# Lift_M.net
KiCad netlist of a schematic drawn in EAGLE
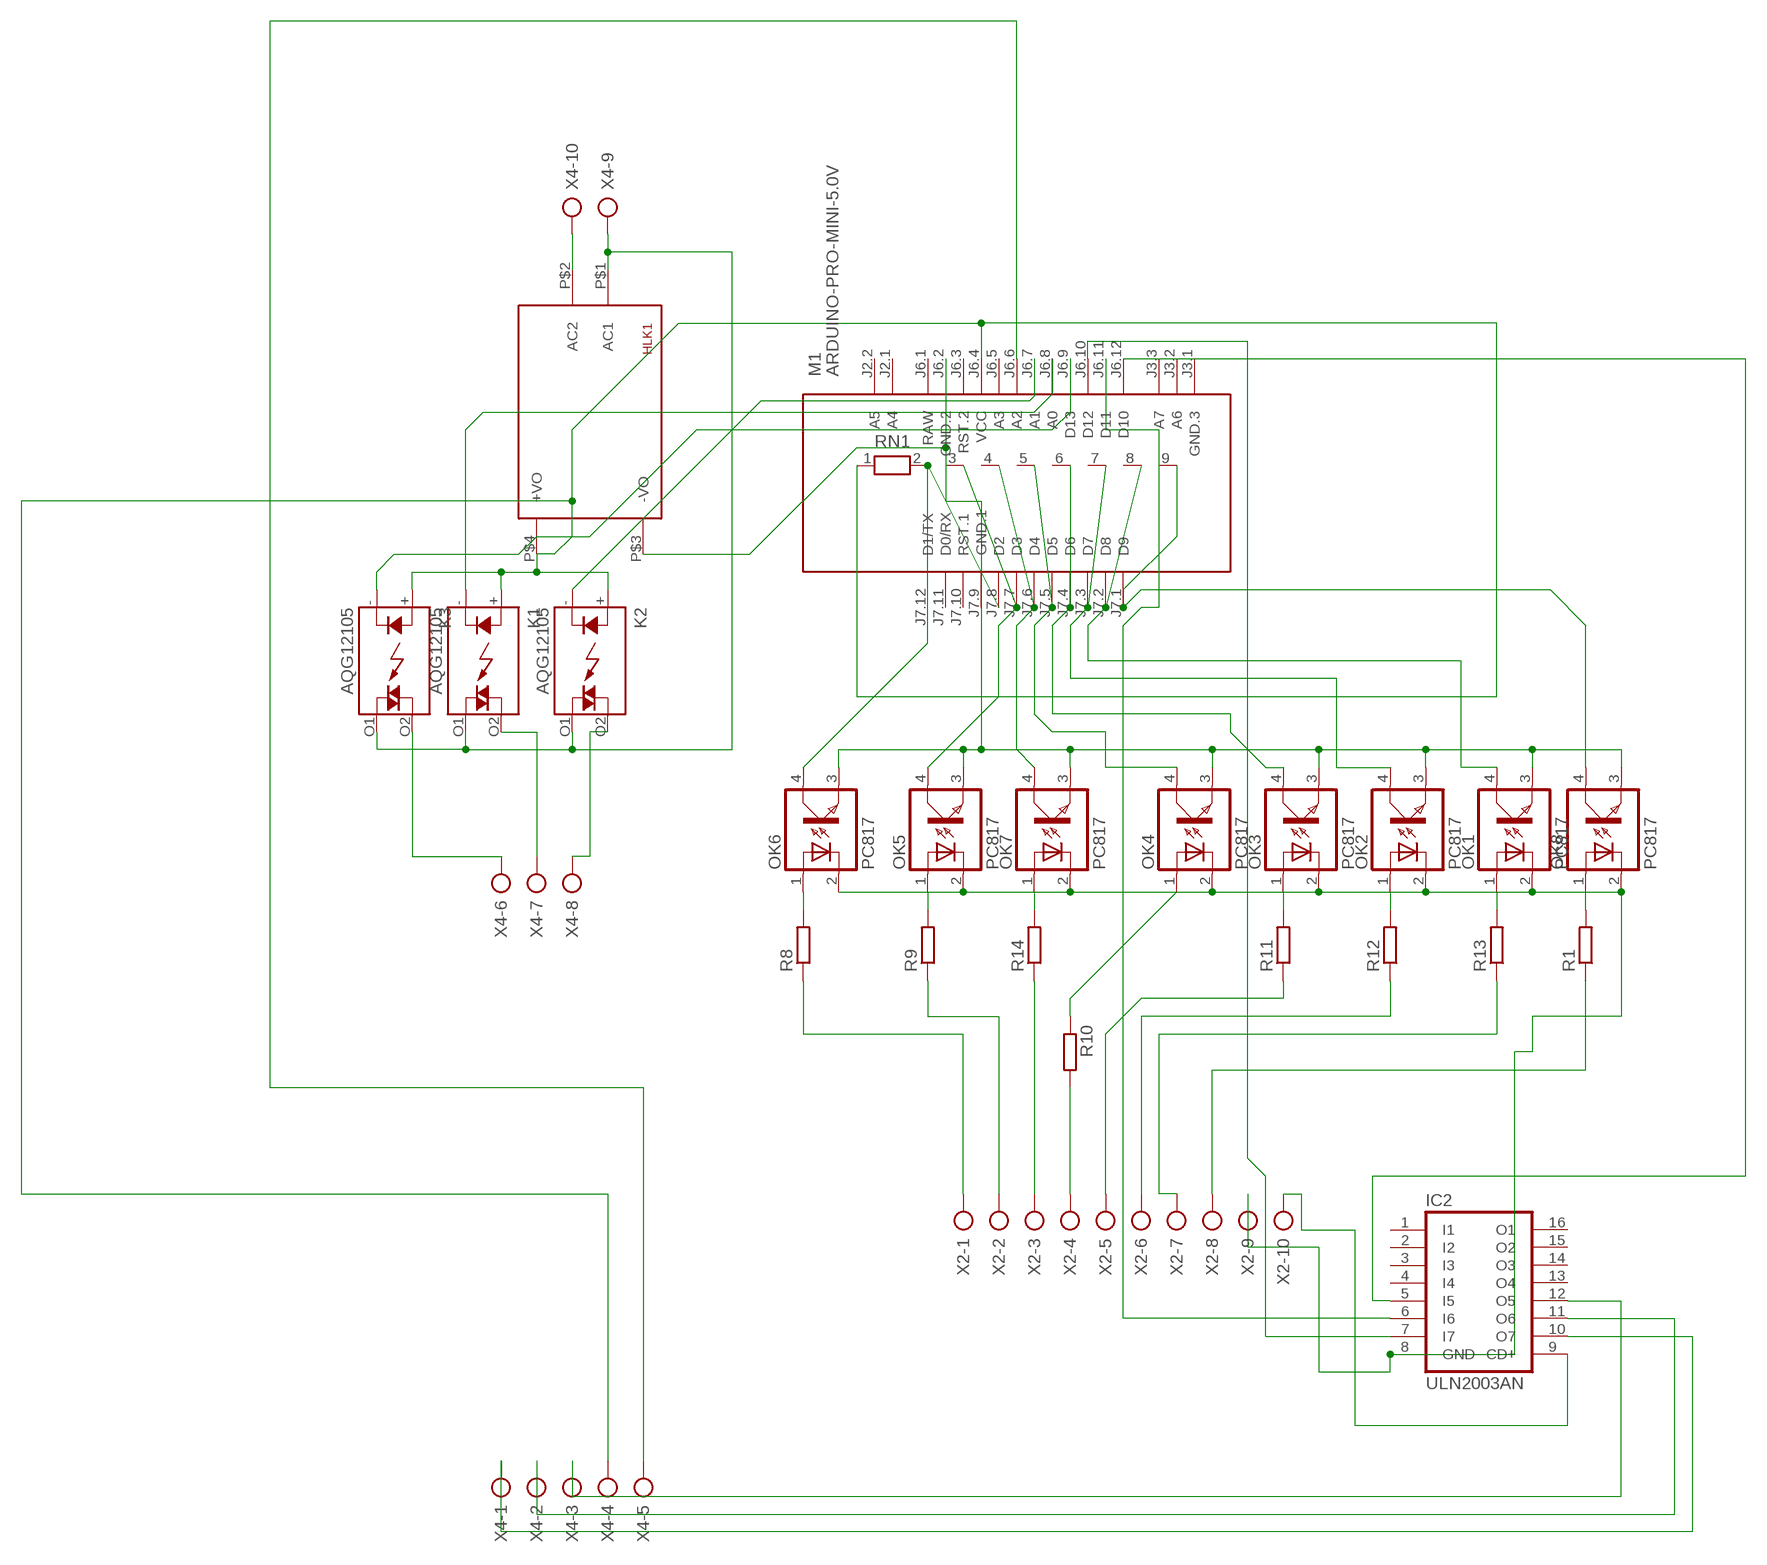
[diagram p0: schematic, sheet 1]

(export (version "E")
  (design (tool "Eeschema 10.0.6"))
  (components
    (comp (ref "HLK1")
      (value "HLK-PM013W")
      (footprint "eagle-import:HLK-PM01")
      (libsource (lib "eagle-import") (part "HLK-PM013W"))
    )
    (comp (ref "IC2")
      (value "ULN2003AN")
      (footprint "eagle-import:DIL16")
      (libsource (lib "eagle-import") (part "ULN2003AN"))
    )
    (comp (ref "K1")
      (value "AQG12105")
      (footprint "eagle-import:AQG")
      (fields (field (name "MF") "AROMAT/ MATSUSHITA"))
      (libsource (lib "eagle-import") (part "AQG12105"))
    )
    (comp (ref "K2")
      (value "AQG12105")
      (footprint "eagle-import:AQG")
      (fields (field (name "MF") "AROMAT/ MATSUSHITA"))
      (libsource (lib "eagle-import") (part "AQG12105"))
    )
    (comp (ref "K3")
      (value "AQG12105")
      (footprint "eagle-import:AQG")
      (fields (field (name "MF") "AROMAT/ MATSUSHITA"))
      (libsource (lib "eagle-import") (part "AQG12105"))
    )
    (comp (ref "M1")
      (value "ARDUINO-PRO-MINI-5.0V")
      (footprint "eagle-import:ARDUINO-PRO-MINI")
      (libsource (lib "eagle-import") (part "ARDUINO-PRO-MINI-5.0V"))
    )
    (comp (ref "OK1")
      (value "PC817")
      (footprint "eagle-import:DIL04")
      (fields (field (name "MPN") "PC817X4J000F"))
      (libsource (lib "eagle-import") (part "PC817"))
    )
    (comp (ref "OK2")
      (value "PC817")
      (footprint "eagle-import:DIL04")
      (fields (field (name "MPN") "PC817X4J000F"))
      (libsource (lib "eagle-import") (part "PC817"))
    )
    (comp (ref "OK3")
      (value "PC817")
      (footprint "eagle-import:DIL04")
      (fields (field (name "MPN") "PC817X4J000F"))
      (libsource (lib "eagle-import") (part "PC817"))
    )
    (comp (ref "OK4")
      (value "PC817")
      (footprint "eagle-import:DIL04")
      (fields (field (name "MPN") "PC817X4J000F"))
      (libsource (lib "eagle-import") (part "PC817"))
    )
    (comp (ref "OK5")
      (value "PC817")
      (footprint "eagle-import:DIL04")
      (fields (field (name "MPN") "PC817X4J000F"))
      (libsource (lib "eagle-import") (part "PC817"))
    )
    (comp (ref "OK6")
      (value "PC817")
      (footprint "eagle-import:DIL04")
      (fields (field (name "MPN") "PC817X4J000F"))
      (libsource (lib "eagle-import") (part "PC817"))
    )
    (comp (ref "OK7")
      (value "PC817")
      (footprint "eagle-import:DIL04")
      (fields (field (name "MPN") "PC817X4J000F"))
      (libsource (lib "eagle-import") (part "PC817"))
    )
    (comp (ref "OK8")
      (value "PC817")
      (footprint "eagle-import:DIL04")
      (fields (field (name "MPN") "PC817X4J000F"))
      (libsource (lib "eagle-import") (part "PC817"))
    )
    (comp (ref "R1")
      (value "R-EU_0204/7")
      (footprint "eagle-import:0204_7")
      (libsource (lib "eagle-import") (part "R-EU_0204/7"))
    )
    (comp (ref "R8")
      (value "R-EU_0204/7")
      (footprint "eagle-import:0204_7")
      (libsource (lib "eagle-import") (part "R-EU_0204/7"))
    )
    (comp (ref "R9")
      (value "R-EU_0204/7")
      (footprint "eagle-import:0204_7")
      (libsource (lib "eagle-import") (part "R-EU_0204/7"))
    )
    (comp (ref "R10")
      (value "R-EU_0204/7")
      (footprint "eagle-import:0204_7")
      (libsource (lib "eagle-import") (part "R-EU_0204/7"))
    )
    (comp (ref "R11")
      (value "R-EU_0204/7")
      (footprint "eagle-import:0204_7")
      (libsource (lib "eagle-import") (part "R-EU_0204/7"))
    )
    (comp (ref "R12")
      (value "R-EU_0204/7")
      (footprint "eagle-import:0204_7")
      (libsource (lib "eagle-import") (part "R-EU_0204/7"))
    )
    (comp (ref "R13")
      (value "R-EU_0204/7")
      (footprint "eagle-import:0204_7")
      (libsource (lib "eagle-import") (part "R-EU_0204/7"))
    )
    (comp (ref "R14")
      (value "R-EU_0204/7")
      (footprint "eagle-import:0204_7")
      (libsource (lib "eagle-import") (part "R-EU_0204/7"))
    )
    (comp (ref "RN1")
      (value "RN08")
      (footprint "eagle-import:RN-9")
      (libsource (lib "eagle-import") (part "RN08"))
    )
    (comp (ref "X2")
      (value "AK300/10")
      (footprint "eagle-import:AK300_10")
      (libsource (lib "eagle-import") (part "AK300/10"))
    )
    (comp (ref "X4")
      (value "AK300/10")
      (footprint "eagle-import:AK300_10")
      (libsource (lib "eagle-import") (part "AK300/10"))
    )
  )
  (nets
    (net (code "1") (name "/RAW") (class "Default")
      (node (ref "M1") (pin "J6.1") (pinfunction "RAW_J6.1") (pintype "power_in"))
    )
    (net (code "2") (name "Net-(HLK1-+VO)") (class "Default")
      (node (ref "HLK1") (pin "P$4") (pinfunction "+VO_P$4") (pintype "bidirectional"))
      (node (ref "K1") (pin "+") (pinfunction "A_+") (pintype "passive"))
      (node (ref "K2") (pin "+") (pinfunction "A_+") (pintype "passive"))
      (node (ref "K3") (pin "+") (pinfunction "A_+") (pintype "passive"))
      (node (ref "M1") (pin "J6.4") (pinfunction "VCC_J6.4") (pintype "power_in"))
      (node (ref "RN1") (pin "1") (pinfunction "1_1") (pintype "passive"))
      (node (ref "X4") (pin "4") (pinfunction "KL_4") (pintype "passive"))
    )
    (net (code "3") (name "Net-(HLK1--VO)") (class "Default")
      (node (ref "HLK1") (pin "P$3") (pinfunction "-VO_P$3") (pintype "bidirectional"))
      (node (ref "M1") (pin "J6.2") (pinfunction "GND.2_J6.2") (pintype "power_in"))
      (node (ref "M1") (pin "J7.9") (pinfunction "GND.1_J7.9") (pintype "power_in"))
      (node (ref "OK1") (pin "3") (pinfunction "EMIT_3") (pintype "passive"))
      (node (ref "OK2") (pin "3") (pinfunction "EMIT_3") (pintype "passive"))
      (node (ref "OK3") (pin "3") (pinfunction "EMIT_3") (pintype "passive"))
      (node (ref "OK4") (pin "3") (pinfunction "EMIT_3") (pintype "passive"))
      (node (ref "OK5") (pin "3") (pinfunction "EMIT_3") (pintype "passive"))
      (node (ref "OK6") (pin "3") (pinfunction "EMIT_3") (pintype "passive"))
      (node (ref "OK7") (pin "3") (pinfunction "EMIT_3") (pintype "passive"))
      (node (ref "OK8") (pin "3") (pinfunction "EMIT_3") (pintype "passive"))
    )
    (net (code "4") (name "Net-(HLK1-AC1)") (class "Default")
      (node (ref "HLK1") (pin "P$1") (pinfunction "AC1_P$1") (pintype "bidirectional"))
      (node (ref "K1") (pin "O1") (pinfunction "DS2_O1") (pintype "passive"))
      (node (ref "K2") (pin "O1") (pinfunction "DS2_O1") (pintype "passive"))
      (node (ref "K3") (pin "O1") (pinfunction "DS2_O1") (pintype "passive"))
      (node (ref "X4") (pin "9") (pinfunction "KL_9") (pintype "passive"))
    )
    (net (code "5") (name "Net-(HLK1-AC2)") (class "Default")
      (node (ref "HLK1") (pin "P$2") (pinfunction "AC2_P$2") (pintype "bidirectional"))
      (node (ref "X4") (pin "10") (pinfunction "KL_10") (pintype "passive"))
    )
    (net (code "6") (name "Net-(IC2-CD+)") (class "Default")
      (node (ref "IC2") (pin "9") (pinfunction "CD+_9") (pintype "passive"))
      (node (ref "X2") (pin "10") (pinfunction "KL_10") (pintype "passive"))
    )
    (net (code "7") (name "Net-(IC2-GND)") (class "Default")
      (node (ref "IC2") (pin "8") (pinfunction "GND_8") (pintype "power_in"))
      (node (ref "OK1") (pin "2") (pinfunction "C_2") (pintype "passive"))
      (node (ref "OK2") (pin "2") (pinfunction "C_2") (pintype "passive"))
      (node (ref "OK3") (pin "2") (pinfunction "C_2") (pintype "passive"))
      (node (ref "OK4") (pin "2") (pinfunction "C_2") (pintype "passive"))
      (node (ref "OK5") (pin "2") (pinfunction "C_2") (pintype "passive"))
      (node (ref "OK6") (pin "2") (pinfunction "C_2") (pintype "passive"))
      (node (ref "OK7") (pin "2") (pinfunction "C_2") (pintype "passive"))
      (node (ref "OK8") (pin "2") (pinfunction "C_2") (pintype "passive"))
      (node (ref "X2") (pin "9") (pinfunction "KL_9") (pintype "passive"))
    )
    (net (code "8") (name "Net-(IC2-I5)") (class "Default")
      (node (ref "IC2") (pin "5") (pinfunction "I5_5") (pintype "input"))
      (node (ref "M1") (pin "J6.12") (pinfunction "D10_J6.12") (pintype "bidirectional"))
    )
    (net (code "9") (name "Net-(IC2-I6)") (class "Default")
      (node (ref "IC2") (pin "6") (pinfunction "I6_6") (pintype "input"))
      (node (ref "M1") (pin "J6.11") (pinfunction "D11_J6.11") (pintype "bidirectional"))
    )
    (net (code "10") (name "Net-(IC2-I7)") (class "Default")
      (node (ref "IC2") (pin "7") (pinfunction "I7_7") (pintype "input"))
      (node (ref "M1") (pin "J6.10") (pinfunction "D12_J6.10") (pintype "bidirectional"))
    )
    (net (code "11") (name "Net-(IC2-O5)") (class "Default")
      (node (ref "IC2") (pin "12") (pinfunction "O5_12") (pintype "open_collector"))
      (node (ref "X4") (pin "3") (pinfunction "KL_3") (pintype "passive"))
    )
    (net (code "12") (name "Net-(IC2-O6)") (class "Default")
      (node (ref "IC2") (pin "11") (pinfunction "O6_11") (pintype "open_collector"))
      (node (ref "X4") (pin "2") (pinfunction "KL_2") (pintype "passive"))
    )
    (net (code "13") (name "Net-(IC2-O7)") (class "Default")
      (node (ref "IC2") (pin "10") (pinfunction "O7_10") (pintype "open_collector"))
      (node (ref "X4") (pin "1") (pinfunction "KL_1") (pintype "passive"))
    )
    (net (code "14") (name "Net-(K1-DS1)") (class "Default")
      (node (ref "K1") (pin "O2") (pinfunction "DS1_O2") (pintype "passive"))
      (node (ref "X4") (pin "7") (pinfunction "KL_7") (pintype "passive"))
    )
    (net (code "15") (name "Net-(K1-K)") (class "Default")
      (node (ref "K1") (pin "-") (pinfunction "K_-") (pintype "passive"))
      (node (ref "M1") (pin "J6.8") (pinfunction "A0_J6.8") (pintype "bidirectional"))
    )
    (net (code "16") (name "Net-(K2-DS1)") (class "Default")
      (node (ref "K2") (pin "O2") (pinfunction "DS1_O2") (pintype "passive"))
      (node (ref "X4") (pin "8") (pinfunction "KL_8") (pintype "passive"))
    )
    (net (code "17") (name "Net-(K2-K)") (class "Default")
      (node (ref "K2") (pin "-") (pinfunction "K_-") (pintype "passive"))
      (node (ref "M1") (pin "J6.7") (pinfunction "A1_J6.7") (pintype "bidirectional"))
    )
    (net (code "18") (name "Net-(K3-DS1)") (class "Default")
      (node (ref "K3") (pin "O2") (pinfunction "DS1_O2") (pintype "passive"))
      (node (ref "X4") (pin "6") (pinfunction "KL_6") (pintype "passive"))
    )
    (net (code "19") (name "Net-(K3-K)") (class "Default")
      (node (ref "K3") (pin "-") (pinfunction "K_-") (pintype "passive"))
      (node (ref "M1") (pin "J6.9") (pinfunction "D13_J6.9") (pintype "bidirectional"))
    )
    (net (code "20") (name "Net-(M1-A2)") (class "Default")
      (node (ref "M1") (pin "J6.6") (pinfunction "A2_J6.6") (pintype "bidirectional"))
      (node (ref "X4") (pin "5") (pinfunction "KL_5") (pintype "passive"))
    )
    (net (code "21") (name "Net-(M1-D2)") (class "Default")
      (node (ref "M1") (pin "J7.8") (pinfunction "D2_J7.8") (pintype "bidirectional"))
      (node (ref "OK6") (pin "4") (pinfunction "COL_4") (pintype "passive"))
      (node (ref "RN1") (pin "2") (pinfunction "2_2") (pintype "passive"))
    )
    (net (code "22") (name "Net-(M1-D3)") (class "Default")
      (node (ref "M1") (pin "J7.7") (pinfunction "D3_J7.7") (pintype "bidirectional"))
      (node (ref "OK5") (pin "4") (pinfunction "COL_4") (pintype "passive"))
      (node (ref "RN1") (pin "3") (pinfunction "3_3") (pintype "passive"))
    )
    (net (code "23") (name "Net-(M1-D4)") (class "Default")
      (node (ref "M1") (pin "J7.6") (pinfunction "D4_J7.6") (pintype "bidirectional"))
      (node (ref "OK7") (pin "4") (pinfunction "COL_4") (pintype "passive"))
      (node (ref "RN1") (pin "4") (pinfunction "4_4") (pintype "passive"))
    )
    (net (code "24") (name "Net-(M1-D5)") (class "Default")
      (node (ref "M1") (pin "J7.5") (pinfunction "D5_J7.5") (pintype "bidirectional"))
      (node (ref "OK4") (pin "4") (pinfunction "COL_4") (pintype "passive"))
      (node (ref "RN1") (pin "5") (pinfunction "5_5") (pintype "passive"))
    )
    (net (code "25") (name "Net-(M1-D6)") (class "Default")
      (node (ref "M1") (pin "J7.4") (pinfunction "D6_J7.4") (pintype "bidirectional"))
      (node (ref "OK3") (pin "4") (pinfunction "COL_4") (pintype "passive"))
      (node (ref "RN1") (pin "6") (pinfunction "6_6") (pintype "passive"))
    )
    (net (code "26") (name "Net-(M1-D7)") (class "Default")
      (node (ref "M1") (pin "J7.3") (pinfunction "D7_J7.3") (pintype "bidirectional"))
      (node (ref "OK2") (pin "4") (pinfunction "COL_4") (pintype "passive"))
      (node (ref "RN1") (pin "7") (pinfunction "7_7") (pintype "passive"))
    )
    (net (code "27") (name "Net-(M1-D8)") (class "Default")
      (node (ref "M1") (pin "J7.2") (pinfunction "D8_J7.2") (pintype "bidirectional"))
      (node (ref "OK1") (pin "4") (pinfunction "COL_4") (pintype "passive"))
      (node (ref "RN1") (pin "8") (pinfunction "8_8") (pintype "passive"))
    )
    (net (code "28") (name "Net-(M1-D9)") (class "Default")
      (node (ref "M1") (pin "J7.1") (pinfunction "D9_J7.1") (pintype "bidirectional"))
      (node (ref "OK8") (pin "4") (pinfunction "COL_4") (pintype "passive"))
      (node (ref "RN1") (pin "9") (pinfunction "9_9") (pintype "passive"))
    )
    (net (code "29") (name "Net-(OK1-A)") (class "Default")
      (node (ref "OK1") (pin "1") (pinfunction "A_1") (pintype "passive"))
      (node (ref "R13") (pin "2") (pinfunction "2_2") (pintype "passive"))
    )
    (net (code "30") (name "Net-(OK2-A)") (class "Default")
      (node (ref "OK2") (pin "1") (pinfunction "A_1") (pintype "passive"))
      (node (ref "R12") (pin "2") (pinfunction "2_2") (pintype "passive"))
    )
    (net (code "31") (name "Net-(OK3-A)") (class "Default")
      (node (ref "OK3") (pin "1") (pinfunction "A_1") (pintype "passive"))
      (node (ref "R11") (pin "2") (pinfunction "2_2") (pintype "passive"))
    )
    (net (code "32") (name "Net-(OK4-A)") (class "Default")
      (node (ref "OK4") (pin "1") (pinfunction "A_1") (pintype "passive"))
      (node (ref "R10") (pin "1") (pinfunction "1_1") (pintype "passive"))
    )
    (net (code "33") (name "Net-(OK5-A)") (class "Default")
      (node (ref "OK5") (pin "1") (pinfunction "A_1") (pintype "passive"))
      (node (ref "R9") (pin "2") (pinfunction "2_2") (pintype "passive"))
    )
    (net (code "34") (name "Net-(OK6-A)") (class "Default")
      (node (ref "OK6") (pin "1") (pinfunction "A_1") (pintype "passive"))
      (node (ref "R8") (pin "2") (pinfunction "2_2") (pintype "passive"))
    )
    (net (code "35") (name "Net-(OK7-A)") (class "Default")
      (node (ref "OK7") (pin "1") (pinfunction "A_1") (pintype "passive"))
      (node (ref "R14") (pin "2") (pinfunction "2_2") (pintype "passive"))
    )
    (net (code "36") (name "Net-(OK8-A)") (class "Default")
      (node (ref "OK8") (pin "1") (pinfunction "A_1") (pintype "passive"))
      (node (ref "R1") (pin "2") (pinfunction "2_2") (pintype "passive"))
    )
    (net (code "37") (name "Net-(X2A-KL)") (class "Default")
      (node (ref "R8") (pin "1") (pinfunction "1_1") (pintype "passive"))
      (node (ref "X2") (pin "1") (pinfunction "KL_1") (pintype "passive"))
    )
    (net (code "38") (name "Net-(X2C-KL)") (class "Default")
      (node (ref "R9") (pin "1") (pinfunction "1_1") (pintype "passive"))
      (node (ref "X2") (pin "2") (pinfunction "KL_2") (pintype "passive"))
    )
    (net (code "39") (name "Net-(X2D-KL)") (class "Default")
      (node (ref "R14") (pin "1") (pinfunction "1_1") (pintype "passive"))
      (node (ref "X2") (pin "3") (pinfunction "KL_3") (pintype "passive"))
    )
    (net (code "40") (name "Net-(X2E-KL)") (class "Default")
      (node (ref "R10") (pin "2") (pinfunction "2_2") (pintype "passive"))
      (node (ref "X2") (pin "4") (pinfunction "KL_4") (pintype "passive"))
    )
    (net (code "41") (name "Net-(X2F-KL)") (class "Default")
      (node (ref "R11") (pin "1") (pinfunction "1_1") (pintype "passive"))
      (node (ref "X2") (pin "5") (pinfunction "KL_5") (pintype "passive"))
    )
    (net (code "42") (name "Net-(X2G-KL)") (class "Default")
      (node (ref "R12") (pin "1") (pinfunction "1_1") (pintype "passive"))
      (node (ref "X2") (pin "6") (pinfunction "KL_6") (pintype "passive"))
    )
    (net (code "43") (name "Net-(X2H-KL)") (class "Default")
      (node (ref "R13") (pin "1") (pinfunction "1_1") (pintype "passive"))
      (node (ref "X2") (pin "7") (pinfunction "KL_7") (pintype "passive"))
    )
    (net (code "44") (name "Net-(X2I-KL)") (class "Default")
      (node (ref "R1") (pin "1") (pinfunction "1_1") (pintype "passive"))
      (node (ref "X2") (pin "8") (pinfunction "KL_8") (pintype "passive"))
    )
    (net (code "45") (name "unconnected-(IC2-I1-Pad1)") (class "Default")
      (node (ref "IC2") (pin "1") (pinfunction "I1_1") (pintype "input"))
    )
    (net (code "46") (name "unconnected-(IC2-I2-Pad2)") (class "Default")
      (node (ref "IC2") (pin "2") (pinfunction "I2_2") (pintype "input"))
    )
    (net (code "47") (name "unconnected-(IC2-I3-Pad3)") (class "Default")
      (node (ref "IC2") (pin "3") (pinfunction "I3_3") (pintype "input"))
    )
    (net (code "48") (name "unconnected-(IC2-I4-Pad4)") (class "Default")
      (node (ref "IC2") (pin "4") (pinfunction "I4_4") (pintype "input"))
    )
    (net (code "49") (name "unconnected-(IC2-O1-Pad16)") (class "Default")
      (node (ref "IC2") (pin "16") (pinfunction "O1_16") (pintype "open_collector"))
    )
    (net (code "50") (name "unconnected-(IC2-O2-Pad15)") (class "Default")
      (node (ref "IC2") (pin "15") (pinfunction "O2_15") (pintype "open_collector"))
    )
    (net (code "51") (name "unconnected-(IC2-O3-Pad14)") (class "Default")
      (node (ref "IC2") (pin "14") (pinfunction "O3_14") (pintype "open_collector"))
    )
    (net (code "52") (name "unconnected-(IC2-O4-Pad13)") (class "Default")
      (node (ref "IC2") (pin "13") (pinfunction "O4_13") (pintype "open_collector"))
    )
    (net (code "53") (name "unconnected-(M1-A3-PadJ6.5)") (class "Default")
      (node (ref "M1") (pin "J6.5") (pinfunction "A3_J6.5") (pintype "bidirectional"))
    )
    (net (code "54") (name "unconnected-(M1-A4-PadJ2.1)") (class "Default")
      (node (ref "M1") (pin "J2.1") (pinfunction "A4_J2.1") (pintype "bidirectional"))
    )
    (net (code "55") (name "unconnected-(M1-A5-PadJ2.2)") (class "Default")
      (node (ref "M1") (pin "J2.2") (pinfunction "A5_J2.2") (pintype "bidirectional"))
    )
    (net (code "56") (name "unconnected-(M1-A6-PadJ3.2)") (class "Default")
      (node (ref "M1") (pin "J3.2") (pinfunction "A6_J3.2") (pintype "bidirectional"))
    )
    (net (code "57") (name "unconnected-(M1-A7-PadJ3.3)") (class "Default")
      (node (ref "M1") (pin "J3.3") (pinfunction "A7_J3.3") (pintype "bidirectional"))
    )
    (net (code "58") (name "unconnected-(M1-D0{slash}RX-PadJ7.11)") (class "Default")
      (node (ref "M1") (pin "J7.11") (pinfunction "D0/RX_J7.11") (pintype "bidirectional"))
    )
    (net (code "59") (name "unconnected-(M1-D1{slash}TX-PadJ7.12)") (class "Default")
      (node (ref "M1") (pin "J7.12") (pinfunction "D1/TX_J7.12") (pintype "bidirectional"))
    )
    (net (code "60") (name "unconnected-(M1-GND.3-PadJ3.1)") (class "Default")
      (node (ref "M1") (pin "J3.1") (pinfunction "GND.3_J3.1") (pintype "bidirectional"))
    )
    (net (code "61") (name "unconnected-(M1-RST.1-PadJ7.10)") (class "Default")
      (node (ref "M1") (pin "J7.10") (pinfunction "RST.1_J7.10") (pintype "bidirectional"))
    )
    (net (code "62") (name "unconnected-(M1-RST.2-PadJ6.3)") (class "Default")
      (node (ref "M1") (pin "J6.3") (pinfunction "RST.2_J6.3") (pintype "bidirectional"))
    )
  )
)
